# subDIn.net
KiCad netlist of a schematic drawn in Altium Designer
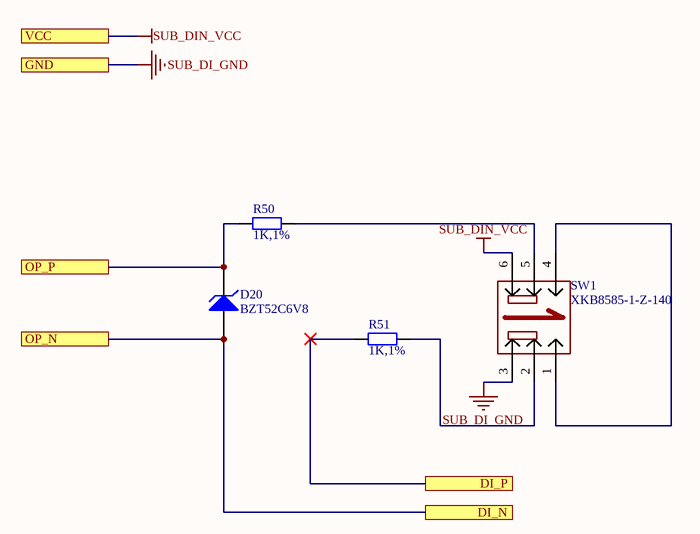
[diagram p0: subDIn.SchDoc]

(export (version "E")
  (design (tool "Eeschema 10.0.6"))
  (components
    (comp (ref "D20")
      (value "BZT52C6V8")
      (footprint "SOD-123")
      (description "Surface Mount Zener Diode")
      (fields (field (name "PUBLISHER") "Altium Limited"))
      (libsource (lib "Vishay Lite-On Discrete Diode") (part "BZT52C6V8"))
    )
    (comp (ref "R50")
      (value "1K,1%")
      (footprint "R0603")
      (description "电阻")
      (libsource (lib "电阻电容") (part "电阻"))
    )
    (comp (ref "R51")
      (value "1K,1%")
      (footprint "R0603")
      (description "电阻")
      (libsource (lib "电阻电容") (part "电阻"))
    )
    (comp (ref "SW1")
      (value "XKB8585-1-Z-140")
      (footprint "SW-TH_6P-L8.6-W8.6-P2.50-LS5.4")
      (description "按键开关 六脚 外扣 有声自锁")
      (libsource (lib "Schlib1") (part "XKB8585-1-Z-140"))
    )
  )
  (nets
    (net (code "1") (name "/DI_N") (class "Default")
      (node (ref "D20") (pin "1") (pinfunction "A_1") (pintype "passive"))
    )
    (net (code "2") (name "/DI_P") (class "Default")
      (node (ref "R51") (pin "2") (pinfunction "2_2") (pintype "passive+no_connect"))
    )
    (net (code "3") (name "/OP_P") (class "Default")
      (node (ref "D20") (pin "2") (pinfunction "K_2") (pintype "passive"))
      (node (ref "R50") (pin "2") (pinfunction "2_2") (pintype "passive"))
    )
    (net (code "4") (name "Net-(R50-Pad1)") (class "Default")
      (node (ref "R50") (pin "1") (pinfunction "1_1") (pintype "passive"))
      (node (ref "SW1") (pin "5") (pinfunction "5_5") (pintype "passive"))
    )
    (net (code "5") (name "Net-(R51-Pad1)") (class "Default")
      (node (ref "R51") (pin "1") (pinfunction "1_1") (pintype "passive"))
      (node (ref "SW1") (pin "2") (pinfunction "2_2") (pintype "passive"))
    )
    (net (code "6") (name "Net-(SW1-Pad1)") (class "Default")
      (node (ref "SW1") (pin "1") (pinfunction "1_1") (pintype "passive"))
      (node (ref "SW1") (pin "4") (pinfunction "4_4") (pintype "passive"))
    )
    (net (code "7") (name "SUB_DIN_VCC") (class "Default")
      (node (ref "SW1") (pin "6") (pinfunction "6_6") (pintype "passive"))
    )
    (net (code "8") (name "SUB_DI_GND") (class "Default")
      (node (ref "SW1") (pin "3") (pinfunction "3_3") (pintype "passive"))
    )
  )
)
